# schema1.net
KiCad netlist of a schematic drawn in EAGLE
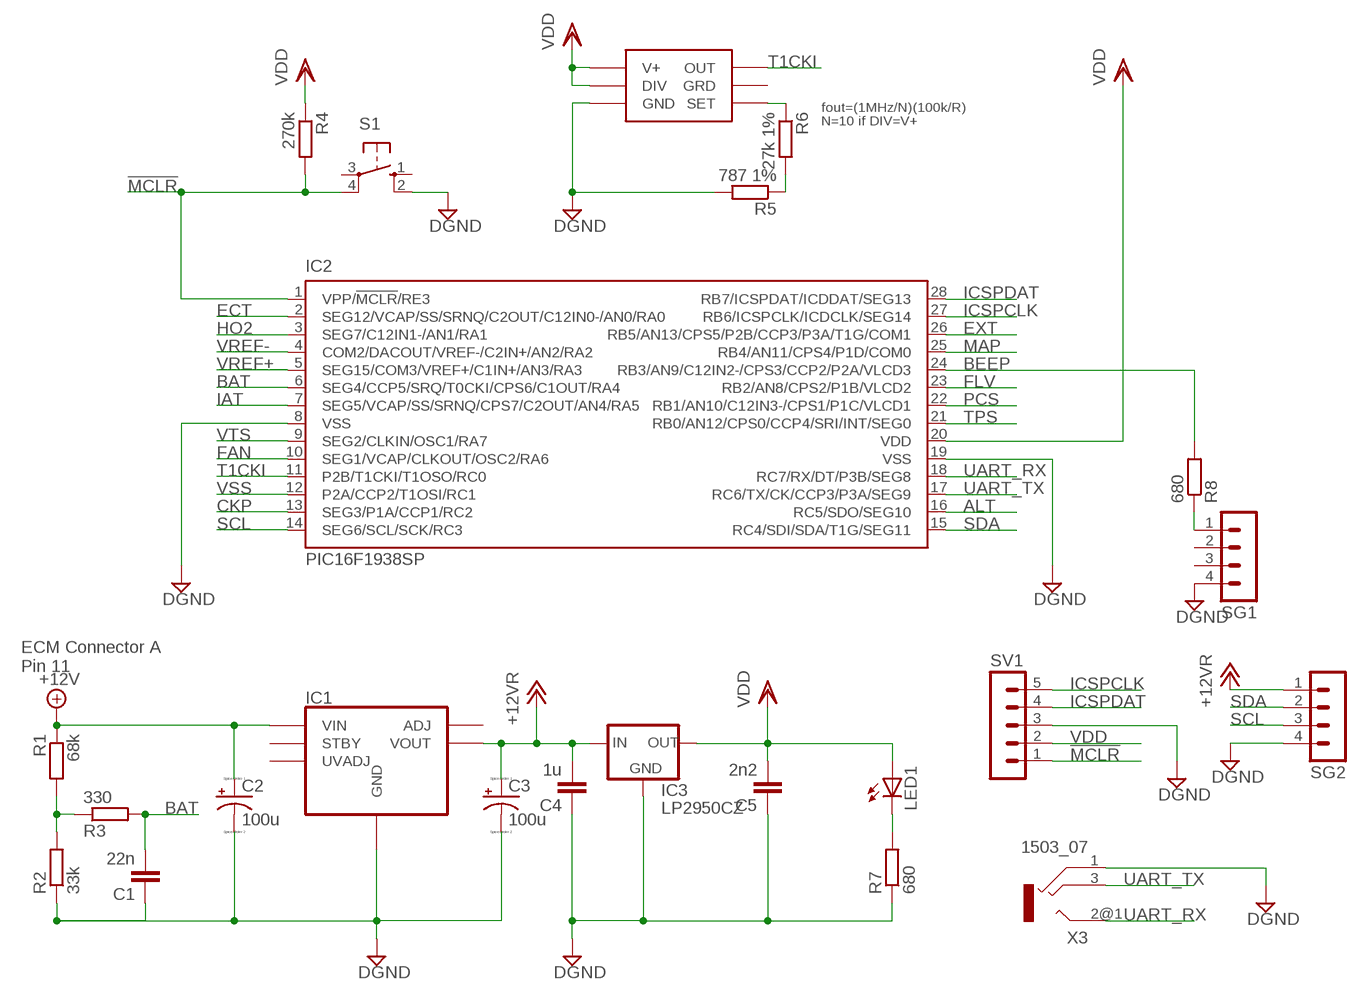
[diagram p0: schematic, sheet 1]
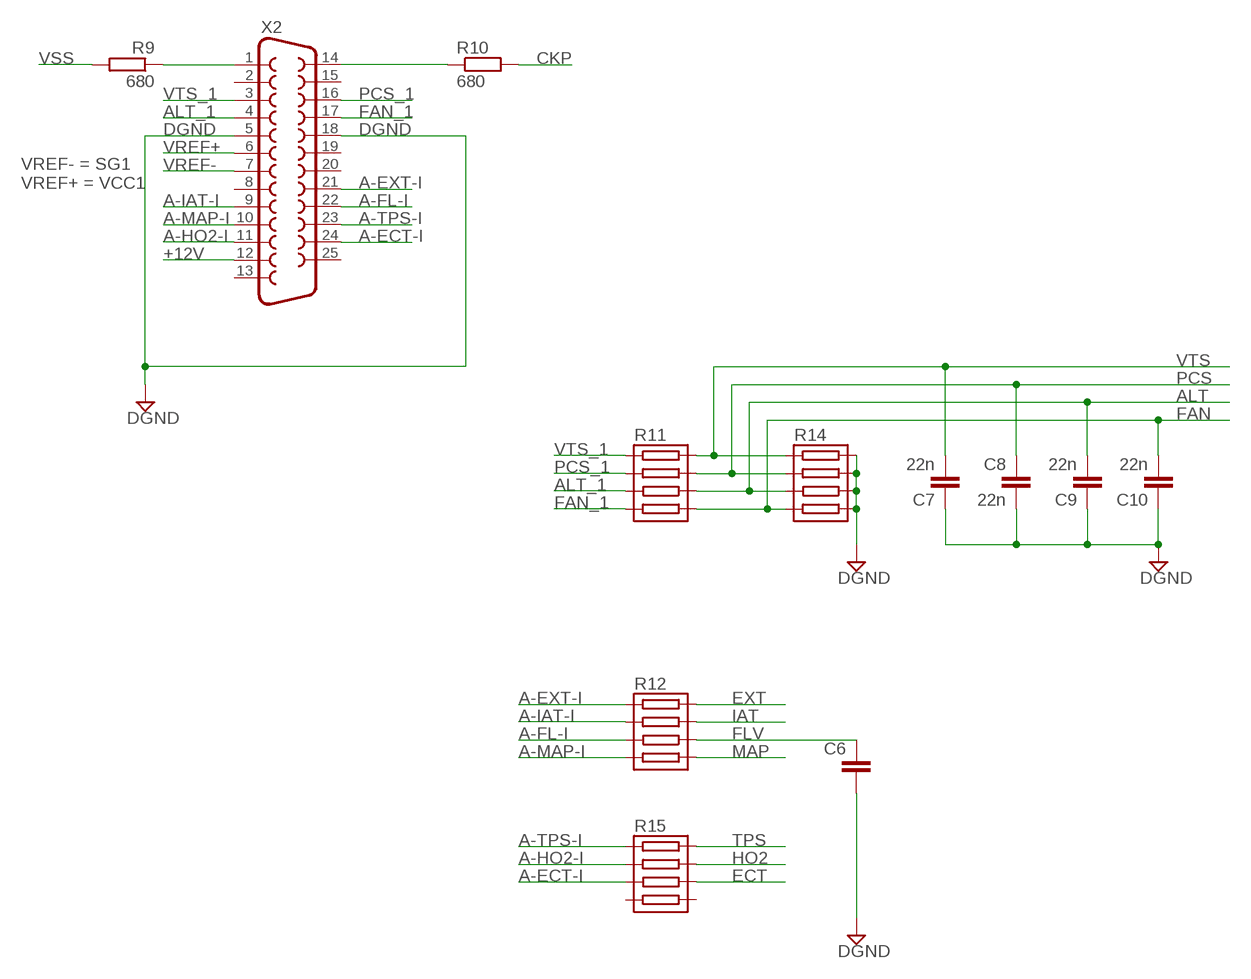
[diagram p1: schematic, sheet 2]

(export (version "E")
  (design (tool "Eeschema 10.0.6"))
  (components
    (comp (ref "C1")
      (value "22n")
      (footprint "eagle-import:C5B3")
      (libsource (lib "eagle-import") (part "C5/3"))
    )
    (comp (ref "C2")
      (value "100u")
      (footprint "eagle-import:E5-10,5")
      (libsource (lib "eagle-import") (part "CPOL-USE5-10.5"))
    )
    (comp (ref "C3")
      (value "100u")
      (footprint "eagle-import:E5-10,5")
      (libsource (lib "eagle-import") (part "CPOL-USE5-10.5"))
    )
    (comp (ref "C4")
      (value "1u")
      (footprint "eagle-import:C5B2.5")
      (libsource (lib "eagle-import") (part "C5/2.5"))
    )
    (comp (ref "C5")
      (value "2n2")
      (footprint "eagle-import:C5B2.5")
      (libsource (lib "eagle-import") (part "C5/2.5"))
    )
    (comp (ref "IC1")
      (value "EXCALIBURPKG1360")
      (footprint "eagle-import:TI_PKG1360")
      (libsource (lib "eagle-import") (part "EXCALIBURPKG1360"))
    )
    (comp (ref "IC2")
      (value "PIC16F1938SP")
      (footprint "eagle-import:DIL28-3")
      (fields (field (name "MPN") "PIC16F1938-I/SP"))
      (libsource (lib "eagle-import") (part "PIC16F19SP38"))
    )
    (comp (ref "IC3")
      (value "LP2950CZ")
      (footprint "eagle-import:TO92")
      (libsource (lib "eagle-import") (part "LP2950?CZ-5.0"))
    )
    (comp (ref "IC4")
      (value "LTC6906")
      (footprint "eagle-import:TSOT23-6")
      (libsource (lib "eagle-import") (part "LTC6906"))
    )
    (comp (ref "LED1")
      (value "LEDCHIP-LED0805")
      (footprint "eagle-import:CHIP-LED0805")
      (libsource (lib "eagle-import") (part "LEDCHIP-LED0805"))
    )
    (comp (ref "R1")
      (value "68k")
      (footprint "eagle-import:M1206")
      (libsource (lib "eagle-import") (part "R-EU_M1206"))
    )
    (comp (ref "R2")
      (value "33k")
      (footprint "eagle-import:M1206")
      (libsource (lib "eagle-import") (part "R-EU_M1206"))
    )
    (comp (ref "R3")
      (value "330")
      (footprint "eagle-import:M1206")
      (libsource (lib "eagle-import") (part "R-EU_M1206"))
    )
    (comp (ref "R4")
      (value "270k")
      (footprint "eagle-import:M1206")
      (libsource (lib "eagle-import") (part "R-EU_M1206"))
    )
    (comp (ref "R5")
      (value "787 1%")
      (footprint "eagle-import:M0805")
      (libsource (lib "eagle-import") (part "R-EU_M0805"))
    )
    (comp (ref "R6")
      (value "27k 1%")
      (footprint "eagle-import:M0805")
      (libsource (lib "eagle-import") (part "R-EU_M0805"))
    )
    (comp (ref "R7")
      (value "680")
      (footprint "eagle-import:M1206")
      (libsource (lib "eagle-import") (part "R-EU_M1206"))
    )
    (comp (ref "R8")
      (value "680")
      (footprint "eagle-import:M1206")
      (libsource (lib "eagle-import") (part "R-EU_M1206"))
    )
    (comp (ref "S1")
      (value "10-XX")
      (footprint "eagle-import:B3F-10XX")
      (fields (field (name "MPN") "B3F-1000"))
      (libsource (lib "eagle-import") (part "10-XX"))
    )
    (comp (ref "SG1")
      (value "MA04-1")
      (footprint "eagle-import:MA04-1")
      (libsource (lib "eagle-import") (part "MA04-1"))
    )
    (comp (ref "SG2")
      (value "MA04-1")
      (footprint "eagle-import:MA04-1")
      (libsource (lib "eagle-import") (part "MA04-1"))
    )
    (comp (ref "SV1")
      (value "MA05-1")
      (footprint "eagle-import:MA05-1")
      (libsource (lib "eagle-import") (part "MA05-1"))
    )
    (comp (ref "X3")
      (value "1503_07")
      (footprint "eagle-import:1503_07")
      (libsource (lib "eagle-import") (part "1503_?07"))
    )
    (comp (ref "C6")
      (value "C5/3")
      (footprint "eagle-import:C5B3")
      (libsource (lib "eagle-import") (part "C5/3"))
    )
    (comp (ref "C7")
      (value "22n")
      (footprint "eagle-import:C5B3")
      (libsource (lib "eagle-import") (part "C5/3"))
    )
    (comp (ref "C8")
      (value "22n")
      (footprint "eagle-import:C5B3")
      (libsource (lib "eagle-import") (part "C5/3"))
    )
    (comp (ref "C9")
      (value "22n")
      (footprint "eagle-import:C5B3")
      (libsource (lib "eagle-import") (part "C5/3"))
    )
    (comp (ref "C10")
      (value "22n")
      (footprint "eagle-import:C5B3")
      (libsource (lib "eagle-import") (part "C5/3"))
    )
    (comp (ref "R9")
      (value "680")
      (footprint "eagle-import:M1206")
      (libsource (lib "eagle-import") (part "R-EU_M1206"))
    )
    (comp (ref "R10")
      (value "680")
      (footprint "eagle-import:M1206")
      (libsource (lib "eagle-import") (part "R-EU_M1206"))
    )
    (comp (ref "R11")
      (value "RESISTOR_ARRAY")
      (footprint "eagle-import:RES_ARRAY_DIP_4")
      (fields (field (name "MPN") "SIL 8-4") (field (name "R17") "68K"))
      (libsource (lib "eagle-import") (part "RESISTOR_ARRAY"))
    )
    (comp (ref "R12")
      (value "RESISTOR_ARRAY")
      (footprint "eagle-import:RES_ARRAY_DIP_4")
      (fields (field (name "MPN") "SIL 8-4") (field (name "R17") "68K"))
      (libsource (lib "eagle-import") (part "RESISTOR_ARRAY"))
    )
    (comp (ref "R14")
      (value "RESISTOR_ARRAY")
      (footprint "eagle-import:RES_ARRAY_DIP_4")
      (fields (field (name "MPN") "SIL 8-4"))
      (libsource (lib "eagle-import") (part "RESISTOR_ARRAY"))
    )
    (comp (ref "R15")
      (value "RESISTOR_ARRAY")
      (footprint "eagle-import:RES_ARRAY_DIP_4")
      (fields (field (name "MPN") "SIL 8-4") (field (name "R17") "68K"))
      (libsource (lib "eagle-import") (part "RESISTOR_ARRAY"))
    )
    (comp (ref "X2")
      (value "F25H")
      (footprint "eagle-import:F25H")
      (libsource (lib "eagle-import") (part "F25H"))
    )
  )
  (nets
    (net (code "1") (name "+12V") (class "Default")
      (node (ref "C2") (pin "+") (pinfunction "+_+") (pintype "passive"))
      (node (ref "IC1") (pin "P$4") (pinfunction "VIN_P$4") (pintype "bidirectional"))
      (node (ref "IC1") (pin "P$5") (pinfunction "VIN_P$5") (pintype "bidirectional"))
      (node (ref "IC1") (pin "P$6") (pinfunction "VIN_P$6") (pintype "bidirectional"))
      (node (ref "R1") (pin "1") (pinfunction "1_1") (pintype "passive"))
      (node (ref "X2") (pin "12") (pinfunction "12_12") (pintype "passive"))
    )
    (net (code "2") (name "+12VR") (class "Default")
      (node (ref "C3") (pin "+") (pinfunction "+_+") (pintype "passive"))
      (node (ref "C4") (pin "2") (pinfunction "2_2") (pintype "passive"))
      (node (ref "IC1") (pin "P$11") (pinfunction "VOUT_P$11") (pintype "bidirectional"))
      (node (ref "IC1") (pin "P$12") (pinfunction "VOUT_P$12") (pintype "bidirectional"))
      (node (ref "IC1") (pin "P$13") (pinfunction "VOUT_P$13") (pintype "bidirectional"))
      (node (ref "IC3") (pin "3") (pinfunction "IN_3") (pintype "input"))
      (node (ref "SG2") (pin "1") (pinfunction "1_1") (pintype "passive"))
    )
    (net (code "3") (name "A-ECT-I") (class "Default")
      (node (ref "R15") (pin "P$5") (pinfunction "P$5_P$5") (pintype "passive"))
      (node (ref "X2") (pin "24") (pinfunction "24_24") (pintype "passive"))
    )
    (net (code "4") (name "A-EXT-I") (class "Default")
      (node (ref "R12") (pin "P$1") (pinfunction "P$1_P$1") (pintype "passive"))
      (node (ref "X2") (pin "21") (pinfunction "21_21") (pintype "passive"))
    )
    (net (code "5") (name "A-FL-I") (class "Default")
      (node (ref "R12") (pin "P$5") (pinfunction "P$5_P$5") (pintype "passive"))
      (node (ref "X2") (pin "22") (pinfunction "22_22") (pintype "passive"))
    )
    (net (code "6") (name "A-HO2-I") (class "Default")
      (node (ref "R15") (pin "P$3") (pinfunction "P$3_P$3") (pintype "passive"))
      (node (ref "X2") (pin "11") (pinfunction "11_11") (pintype "passive"))
    )
    (net (code "7") (name "A-IAT-I") (class "Default")
      (node (ref "R12") (pin "P$3") (pinfunction "P$3_P$3") (pintype "passive"))
      (node (ref "X2") (pin "9") (pinfunction "9_9") (pintype "passive"))
    )
    (net (code "8") (name "A-MAP-I") (class "Default")
      (node (ref "R12") (pin "P$7") (pinfunction "P$7_P$7") (pintype "passive"))
      (node (ref "X2") (pin "10") (pinfunction "10_10") (pintype "passive"))
    )
    (net (code "9") (name "A-TPS-I") (class "Default")
      (node (ref "R15") (pin "P$1") (pinfunction "P$1_P$1") (pintype "passive"))
      (node (ref "X2") (pin "23") (pinfunction "23_23") (pintype "passive"))
    )
    (net (code "10") (name "ALT") (class "Default")
      (node (ref "C9") (pin "2") (pinfunction "2_2") (pintype "passive"))
      (node (ref "IC2") (pin "16") (pinfunction "RC5/SDO/SEG10_16") (pintype "bidirectional"))
      (node (ref "R11") (pin "P$6") (pinfunction "P$6_P$6") (pintype "passive"))
      (node (ref "R14") (pin "P$5") (pinfunction "P$5_P$5") (pintype "passive"))
    )
    (net (code "11") (name "ALT_1") (class "Default")
      (node (ref "R11") (pin "P$5") (pinfunction "P$5_P$5") (pintype "passive"))
      (node (ref "X2") (pin "4") (pinfunction "4_4") (pintype "passive"))
    )
    (net (code "12") (name "BAT") (class "Default")
      (node (ref "C1") (pin "2") (pinfunction "2_2") (pintype "passive"))
      (node (ref "IC2") (pin "6") (pinfunction "SEG4/CCP5/SRQ/T0CKI/CPS6/C1OUT/RA4_6") (pintype "bidirectional"))
      (node (ref "R3") (pin "2") (pinfunction "2_2") (pintype "passive"))
    )
    (net (code "13") (name "BEEP") (class "Default")
      (node (ref "IC2") (pin "24") (pinfunction "RB3/AN9/C12IN2-/CPS3/CCP2/P2A/VLCD3_24") (pintype "bidirectional"))
      (node (ref "R8") (pin "2") (pinfunction "2_2") (pintype "passive"))
    )
    (net (code "14") (name "CKP") (class "Default")
      (node (ref "IC2") (pin "13") (pinfunction "SEG3/P1A/CCP1/RC2_13") (pintype "bidirectional"))
      (node (ref "R10") (pin "2") (pinfunction "2_2") (pintype "passive"))
    )
    (net (code "15") (name "DGND") (class "Default")
      (node (ref "C1") (pin "1") (pinfunction "1_1") (pintype "passive"))
      (node (ref "C10") (pin "1") (pinfunction "1_1") (pintype "passive"))
      (node (ref "C2") (pin "-") (pinfunction "-_-") (pintype "passive"))
      (node (ref "C3") (pin "-") (pinfunction "-_-") (pintype "passive"))
      (node (ref "C4") (pin "1") (pinfunction "1_1") (pintype "passive"))
      (node (ref "C5") (pin "1") (pinfunction "1_1") (pintype "passive"))
      (node (ref "C6") (pin "2") (pinfunction "2_2") (pintype "passive"))
      (node (ref "C7") (pin "1") (pinfunction "1_1") (pintype "passive"))
      (node (ref "C8") (pin "2") (pinfunction "2_2") (pintype "passive"))
      (node (ref "C9") (pin "1") (pinfunction "1_1") (pintype "passive"))
      (node (ref "IC1") (pin "P$10") (pinfunction "GND_P$10") (pintype "bidirectional"))
      (node (ref "IC1") (pin "P$7") (pinfunction "GND_P$7") (pintype "bidirectional"))
      (node (ref "IC1") (pin "P$8") (pinfunction "GND_P$8") (pintype "bidirectional"))
      (node (ref "IC1") (pin "P$9") (pinfunction "GND_P$9") (pintype "bidirectional"))
      (node (ref "IC2") (pin "19") (pinfunction "VSS_19") (pintype "power_in"))
      (node (ref "IC2") (pin "8") (pinfunction "VSS_8") (pintype "power_in"))
      (node (ref "IC3") (pin "2") (pinfunction "GND_2") (pintype "input"))
      (node (ref "IC4") (pin "2") (pinfunction "GND_2") (pintype "bidirectional"))
      (node (ref "R14") (pin "P$2") (pinfunction "P$2_P$2") (pintype "passive"))
      (node (ref "R14") (pin "P$4") (pinfunction "P$4_P$4") (pintype "passive"))
      (node (ref "R14") (pin "P$6") (pinfunction "P$6_P$6") (pintype "passive"))
      (node (ref "R14") (pin "P$8") (pinfunction "P$8_P$8") (pintype "passive"))
      (node (ref "R2") (pin "1") (pinfunction "1_1") (pintype "passive"))
      (node (ref "R5") (pin "2") (pinfunction "2_2") (pintype "passive"))
      (node (ref "R7") (pin "1") (pinfunction "1_1") (pintype "passive"))
      (node (ref "S1") (pin "2") (pinfunction "S1_2") (pintype "passive"))
      (node (ref "SG1") (pin "4") (pinfunction "4_4") (pintype "passive"))
      (node (ref "SG2") (pin "4") (pinfunction "4_4") (pintype "passive"))
      (node (ref "SV1") (pin "3") (pinfunction "3_3") (pintype "passive"))
      (node (ref "X2") (pin "18") (pinfunction "18_18") (pintype "passive"))
      (node (ref "X2") (pin "5") (pinfunction "5_5") (pintype "passive"))
      (node (ref "X3") (pin "1") (pinfunction "1_1") (pintype "passive"))
    )
    (net (code "16") (name "ECT") (class "Default")
      (node (ref "IC2") (pin "2") (pinfunction "SEG12/VCAP/SS/SRNQ/C2OUT/C12IN0-/AN0/RA0_2") (pintype "bidirectional"))
      (node (ref "R15") (pin "P$6") (pinfunction "P$6_P$6") (pintype "passive"))
    )
    (net (code "17") (name "EXT") (class "Default")
      (node (ref "IC2") (pin "26") (pinfunction "RB5/AN13/CPS5/P2B/CCP3/P3A/T1G/COM1_26") (pintype "bidirectional"))
      (node (ref "R12") (pin "P$2") (pinfunction "P$2_P$2") (pintype "passive"))
    )
    (net (code "18") (name "FAN") (class "Default")
      (node (ref "C10") (pin "2") (pinfunction "2_2") (pintype "passive"))
      (node (ref "IC2") (pin "10") (pinfunction "SEG1/VCAP/CLKOUT/OSC2/RA6_10") (pintype "bidirectional"))
      (node (ref "R11") (pin "P$8") (pinfunction "P$8_P$8") (pintype "passive"))
      (node (ref "R14") (pin "P$7") (pinfunction "P$7_P$7") (pintype "passive"))
    )
    (net (code "19") (name "FAN_1") (class "Default")
      (node (ref "R11") (pin "P$7") (pinfunction "P$7_P$7") (pintype "passive"))
      (node (ref "X2") (pin "17") (pinfunction "17_17") (pintype "passive"))
    )
    (net (code "20") (name "FLV") (class "Default")
      (node (ref "C6") (pin "1") (pinfunction "1_1") (pintype "passive"))
      (node (ref "IC2") (pin "23") (pinfunction "RB2/AN8/CPS2/P1B/VLCD2_23") (pintype "bidirectional"))
      (node (ref "R12") (pin "P$6") (pinfunction "P$6_P$6") (pintype "passive"))
    )
    (net (code "21") (name "HO2") (class "Default")
      (node (ref "IC2") (pin "3") (pinfunction "SEG7/C12IN1-/AN1/RA1_3") (pintype "bidirectional"))
      (node (ref "R15") (pin "P$4") (pinfunction "P$4_P$4") (pintype "passive"))
    )
    (net (code "22") (name "IAT") (class "Default")
      (node (ref "IC2") (pin "7") (pinfunction "SEG5/VCAP/SS/SRNQ/CPS7/C2OUT/AN4/RA5_7") (pintype "bidirectional"))
      (node (ref "R12") (pin "P$4") (pinfunction "P$4_P$4") (pintype "passive"))
    )
    (net (code "23") (name "ICSPCLK") (class "Default")
      (node (ref "IC2") (pin "27") (pinfunction "RB6/ICSPCLK/ICDCLK/SEG14_27") (pintype "bidirectional"))
      (node (ref "SV1") (pin "5") (pinfunction "5_5") (pintype "passive"))
    )
    (net (code "24") (name "ICSPDAT") (class "Default")
      (node (ref "IC2") (pin "28") (pinfunction "RB7/ICSPDAT/ICDDAT/SEG13_28") (pintype "bidirectional"))
      (node (ref "SV1") (pin "4") (pinfunction "4_4") (pintype "passive"))
    )
    (net (code "25") (name "MAP") (class "Default")
      (node (ref "IC2") (pin "25") (pinfunction "RB4/AN11/CPS4/P1D/COM0_25") (pintype "bidirectional"))
      (node (ref "R12") (pin "P$8") (pinfunction "P$8_P$8") (pintype "passive"))
    )
    (net (code "26") (name "Net-(IC4-SET)") (class "Default")
      (node (ref "IC4") (pin "4") (pinfunction "SET_4") (pintype "bidirectional"))
      (node (ref "R6") (pin "1") (pinfunction "1_1") (pintype "passive"))
    )
    (net (code "27") (name "Net-(LED1-PadC)") (class "Default")
      (node (ref "LED1") (pin "C") (pinfunction "C_C") (pintype "passive"))
      (node (ref "R7") (pin "2") (pinfunction "2_2") (pintype "passive"))
    )
    (net (code "28") (name "Net-(R1-Pad2)") (class "Default")
      (node (ref "R1") (pin "2") (pinfunction "2_2") (pintype "passive"))
      (node (ref "R2") (pin "2") (pinfunction "2_2") (pintype "passive"))
      (node (ref "R3") (pin "1") (pinfunction "1_1") (pintype "passive"))
    )
    (net (code "29") (name "Net-(R5-Pad1)") (class "Default")
      (node (ref "R5") (pin "1") (pinfunction "1_1") (pintype "passive"))
      (node (ref "R6") (pin "2") (pinfunction "2_2") (pintype "passive"))
    )
    (net (code "30") (name "Net-(R8-Pad1)") (class "Default")
      (node (ref "R8") (pin "1") (pinfunction "1_1") (pintype "passive"))
      (node (ref "SG1") (pin "1") (pinfunction "1_1") (pintype "passive"))
    )
    (net (code "31") (name "Net-(R9-Pad1)") (class "Default")
      (node (ref "R9") (pin "1") (pinfunction "1_1") (pintype "passive"))
      (node (ref "X2") (pin "1") (pinfunction "1_1") (pintype "passive"))
    )
    (net (code "32") (name "Net-(R10-Pad1)") (class "Default")
      (node (ref "R10") (pin "1") (pinfunction "1_1") (pintype "passive"))
      (node (ref "X2") (pin "14") (pinfunction "14_14") (pintype "passive"))
    )
    (net (code "33") (name "PCS") (class "Default")
      (node (ref "C8") (pin "1") (pinfunction "1_1") (pintype "passive"))
      (node (ref "IC2") (pin "22") (pinfunction "RB1/AN10/C12IN3-/CPS1/P1C/VLCD1_22") (pintype "bidirectional"))
      (node (ref "R11") (pin "P$4") (pinfunction "P$4_P$4") (pintype "passive"))
      (node (ref "R14") (pin "P$3") (pinfunction "P$3_P$3") (pintype "passive"))
    )
    (net (code "34") (name "PCS_1") (class "Default")
      (node (ref "R11") (pin "P$3") (pinfunction "P$3_P$3") (pintype "passive"))
      (node (ref "X2") (pin "16") (pinfunction "16_16") (pintype "passive"))
    )
    (net (code "35") (name "SCL") (class "Default")
      (node (ref "IC2") (pin "14") (pinfunction "SEG6/SCL/SCK/RC3_14") (pintype "bidirectional"))
      (node (ref "SG2") (pin "3") (pinfunction "3_3") (pintype "passive"))
    )
    (net (code "36") (name "SDA") (class "Default")
      (node (ref "IC2") (pin "15") (pinfunction "RC4/SDI/SDA/T1G/SEG11_15") (pintype "bidirectional"))
      (node (ref "SG2") (pin "2") (pinfunction "2_2") (pintype "passive"))
    )
    (net (code "37") (name "T1CKI") (class "Default")
      (node (ref "IC2") (pin "11") (pinfunction "P2B/T1CKI/T1OSO/RC0_11") (pintype "bidirectional"))
      (node (ref "IC4") (pin "1") (pinfunction "OUT_1") (pintype "bidirectional"))
    )
    (net (code "38") (name "TPS") (class "Default")
      (node (ref "IC2") (pin "21") (pinfunction "RB0/AN12/CPS0/CCP4/SRI/INT/SEG0_21") (pintype "bidirectional"))
      (node (ref "R15") (pin "P$2") (pinfunction "P$2_P$2") (pintype "passive"))
    )
    (net (code "39") (name "UART_RX") (class "Default")
      (node (ref "IC2") (pin "18") (pinfunction "RC7/RX/DT/P3B/SEG8_18") (pintype "bidirectional"))
      (node (ref "X3") (pin "2@1") (pinfunction "2_2@1") (pintype "passive"))
    )
    (net (code "40") (name "UART_TX") (class "Default")
      (node (ref "IC2") (pin "17") (pinfunction "RC6/TX/CK/CCP3/P3A/SEG9_17") (pintype "bidirectional"))
      (node (ref "X3") (pin "3") (pinfunction "3_3") (pintype "passive"))
    )
    (net (code "41") (name "VDD") (class "Default")
      (node (ref "C5") (pin "2") (pinfunction "2_2") (pintype "passive"))
      (node (ref "IC2") (pin "20") (pinfunction "VDD_20") (pintype "power_in"))
      (node (ref "IC3") (pin "1") (pinfunction "OUT_1") (pintype "passive"))
      (node (ref "IC4") (pin "3") (pinfunction "DIV_3") (pintype "bidirectional"))
      (node (ref "IC4") (pin "6") (pinfunction "V+_6") (pintype "bidirectional"))
      (node (ref "LED1") (pin "A") (pinfunction "A_A") (pintype "passive"))
      (node (ref "R4") (pin "1") (pinfunction "1_1") (pintype "passive"))
      (node (ref "SV1") (pin "2") (pinfunction "2_2") (pintype "passive"))
    )
    (net (code "42") (name "VREF+") (class "Default")
      (node (ref "IC2") (pin "5") (pinfunction "SEG15/COM3/VREF+/C1IN+/AN3/RA3_5") (pintype "bidirectional"))
      (node (ref "X2") (pin "6") (pinfunction "6_6") (pintype "passive"))
    )
    (net (code "43") (name "VREF-") (class "Default")
      (node (ref "IC2") (pin "4") (pinfunction "COM2/DACOUT/VREF-/C2IN+/AN2/RA2_4") (pintype "bidirectional"))
      (node (ref "X2") (pin "7") (pinfunction "7_7") (pintype "passive"))
    )
    (net (code "44") (name "VSS") (class "Default")
      (node (ref "IC2") (pin "12") (pinfunction "P2A/CCP2/T1OSI/RC1_12") (pintype "bidirectional"))
      (node (ref "R9") (pin "2") (pinfunction "2_2") (pintype "passive"))
    )
    (net (code "45") (name "VTS") (class "Default")
      (node (ref "C7") (pin "2") (pinfunction "2_2") (pintype "passive"))
      (node (ref "IC2") (pin "9") (pinfunction "SEG2/CLKIN/OSC1/RA7_9") (pintype "bidirectional"))
      (node (ref "R11") (pin "P$2") (pinfunction "P$2_P$2") (pintype "passive"))
      (node (ref "R14") (pin "P$1") (pinfunction "P$1_P$1") (pintype "passive"))
    )
    (net (code "46") (name "VTS_1") (class "Default")
      (node (ref "R11") (pin "P$1") (pinfunction "P$1_P$1") (pintype "passive"))
      (node (ref "X2") (pin "3") (pinfunction "3_3") (pintype "passive"))
    )
    (net (code "47") (name "unconnected-(IC1-ADJ-PadP$14)") (class "Default")
      (node (ref "IC1") (pin "P$14") (pinfunction "ADJ_P$14") (pintype "bidirectional"))
    )
    (net (code "48") (name "unconnected-(IC1-STBY-PadP$3)") (class "Default")
      (node (ref "IC1") (pin "P$3") (pinfunction "STBY_P$3") (pintype "bidirectional"))
    )
    (net (code "49") (name "unconnected-(IC1-UVADJ-PadP$2)") (class "Default")
      (node (ref "IC1") (pin "P$2") (pinfunction "UVADJ_P$2") (pintype "bidirectional"))
    )
    (net (code "50") (name "unconnected-(IC4-GRD-Pad5)") (class "Default")
      (node (ref "IC4") (pin "5") (pinfunction "GRD_5") (pintype "bidirectional"))
    )
    (net (code "51") (name "unconnected-(R15-PadP$7)") (class "Default")
      (node (ref "R15") (pin "P$7") (pinfunction "P$7_P$7") (pintype "passive"))
    )
    (net (code "52") (name "unconnected-(R15-PadP$8)") (class "Default")
      (node (ref "R15") (pin "P$8") (pinfunction "P$8_P$8") (pintype "passive"))
    )
    (net (code "53") (name "unconnected-(S1-P-Pad3)") (class "Default")
      (node (ref "S1") (pin "3") (pinfunction "P_3") (pintype "passive"))
    )
    (net (code "54") (name "unconnected-(S1-S-Pad1)") (class "Default")
      (node (ref "S1") (pin "1") (pinfunction "S_1") (pintype "passive"))
    )
    (net (code "55") (name "unconnected-(SG1-Pad2)") (class "Default")
      (node (ref "SG1") (pin "2") (pinfunction "2_2") (pintype "passive"))
    )
    (net (code "56") (name "unconnected-(SG1-Pad3)") (class "Default")
      (node (ref "SG1") (pin "3") (pinfunction "3_3") (pintype "passive"))
    )
    (net (code "57") (name "unconnected-(X2-Pad2)") (class "Default")
      (node (ref "X2") (pin "2") (pinfunction "2_2") (pintype "passive"))
    )
    (net (code "58") (name "unconnected-(X2-Pad8)") (class "Default")
      (node (ref "X2") (pin "8") (pinfunction "8_8") (pintype "passive"))
    )
    (net (code "59") (name "unconnected-(X2-Pad13)") (class "Default")
      (node (ref "X2") (pin "13") (pinfunction "13_13") (pintype "passive"))
    )
    (net (code "60") (name "unconnected-(X2-Pad15)") (class "Default")
      (node (ref "X2") (pin "15") (pinfunction "15_15") (pintype "passive"))
    )
    (net (code "61") (name "unconnected-(X2-Pad19)") (class "Default")
      (node (ref "X2") (pin "19") (pinfunction "19_19") (pintype "passive"))
    )
    (net (code "62") (name "unconnected-(X2-Pad20)") (class "Default")
      (node (ref "X2") (pin "20") (pinfunction "20_20") (pintype "passive"))
    )
    (net (code "63") (name "unconnected-(X2-Pad25)") (class "Default")
      (node (ref "X2") (pin "25") (pinfunction "25_25") (pintype "passive"))
    )
    (net (code "64") (name "unconnected-(X3-2-Pad2@2)") (class "Default")
      (node (ref "X3") (pin "2@2") (pinfunction "2_2@2") (pintype "passive"))
    )
    (net (code "65") (name "~{MCLR}") (class "Default")
      (node (ref "IC2") (pin "1") (pinfunction "VPP/~{MCLR}/RE3_1") (pintype "input"))
      (node (ref "R4") (pin "2") (pinfunction "2_2") (pintype "passive"))
      (node (ref "S1") (pin "4") (pinfunction "P1_4") (pintype "passive"))
      (node (ref "SV1") (pin "1") (pinfunction "1_1") (pintype "passive"))
    )
  )
)
